# MDM00001.net
KiCad netlist of a schematic drawn in EAGLE
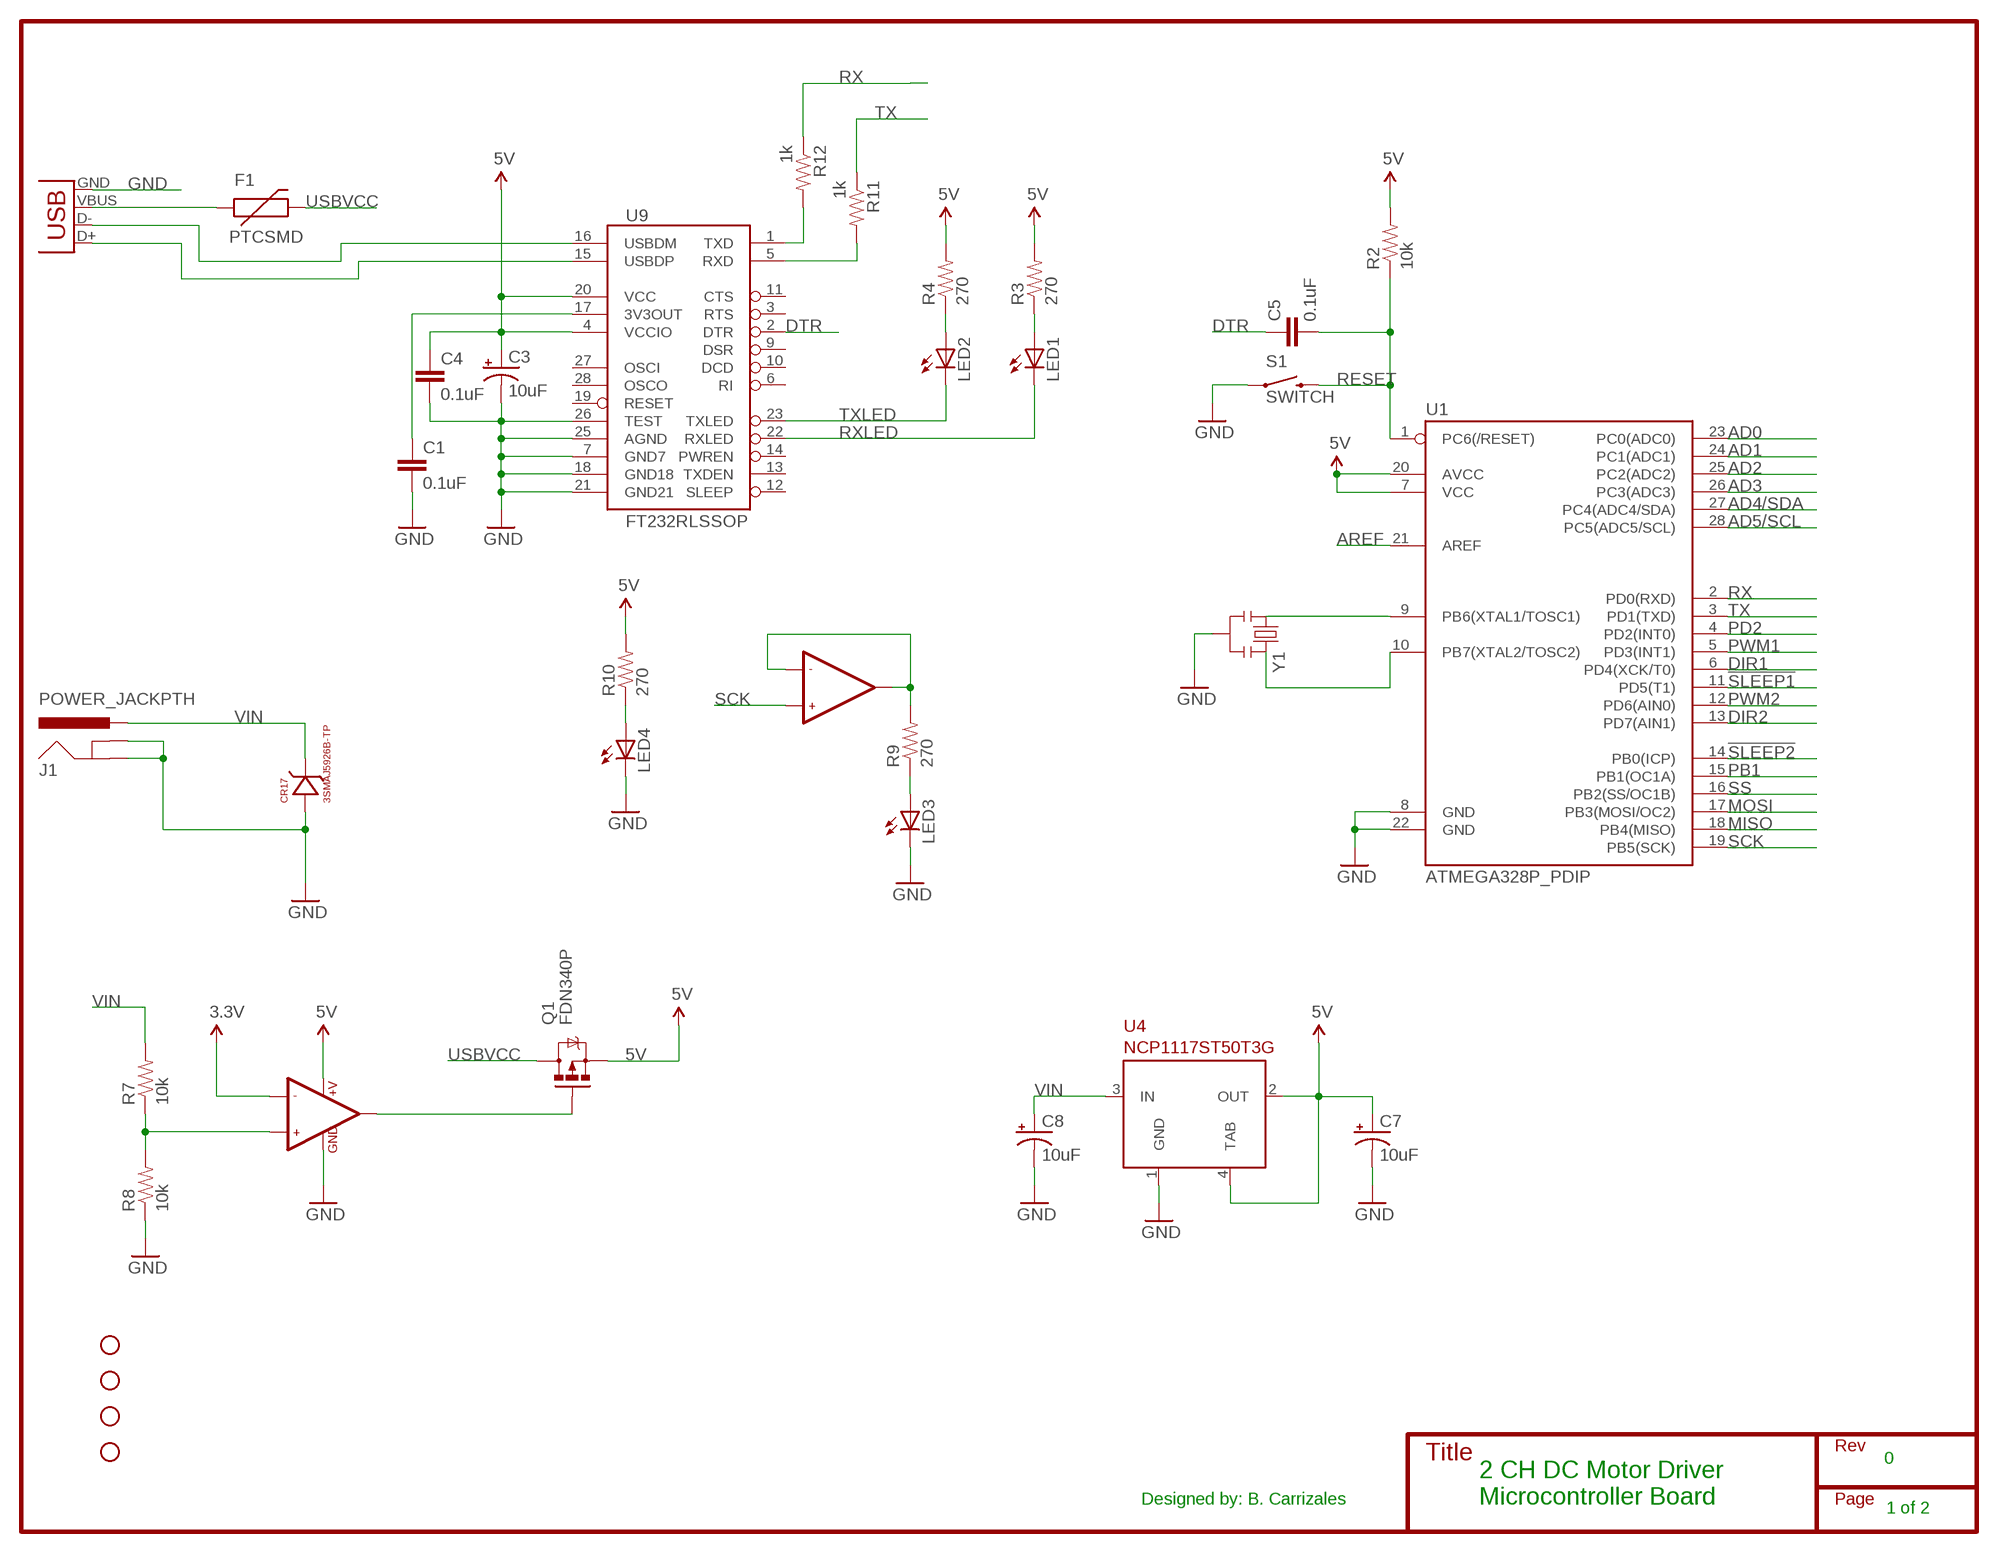
[diagram p0: schematic, sheet 1]
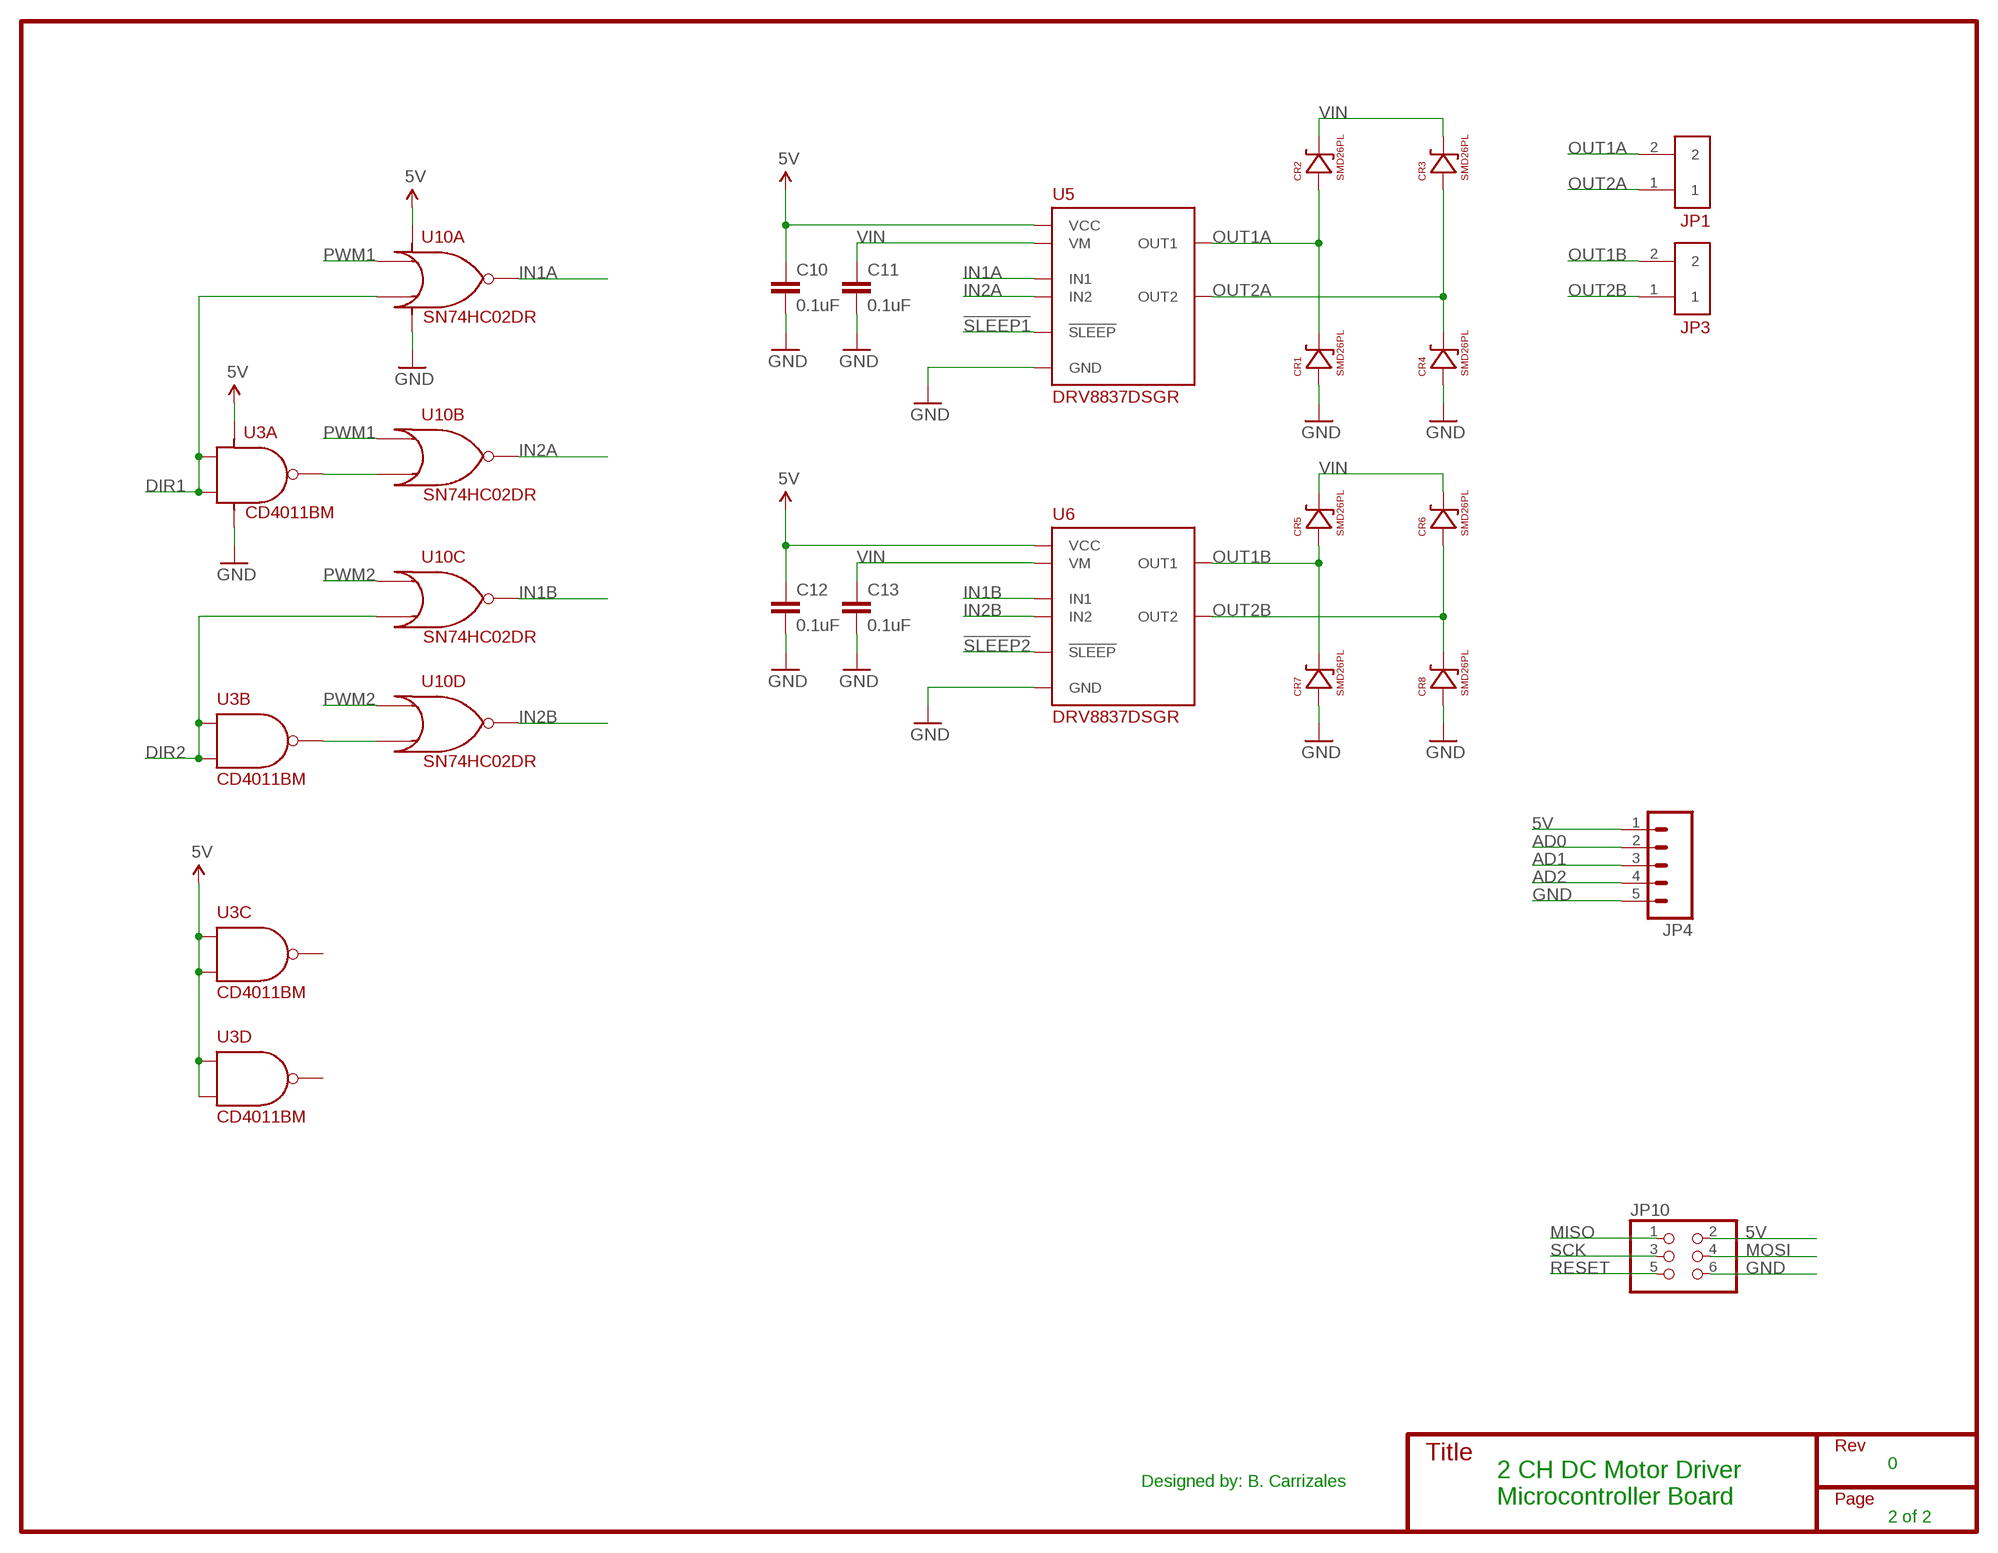
[diagram p1: schematic, sheet 2]

(export (version "E")
  (design (tool "Eeschema 10.0.6"))
  (components
    (comp (ref "C1")
      (value "0.1uF")
      (footprint "eagle-import:0603-CAP")
      (libsource (lib "eagle-import") (part "CAP0603-CAP"))
    )
    (comp (ref "C3")
      (value "10uF")
      (footprint "eagle-import:PANASONIC_BMIN")
      (libsource (lib "eagle-import") (part "CAP_POL_AL"))
    )
    (comp (ref "C4")
      (value "0.1uF")
      (footprint "eagle-import:0603-CAP")
      (libsource (lib "eagle-import") (part "CAP0603-CAP"))
    )
    (comp (ref "C5")
      (value "0.1uF")
      (footprint "eagle-import:0603-CAP")
      (libsource (lib "eagle-import") (part "CAP0603-CAP"))
    )
    (comp (ref "C7")
      (value "10uF")
      (footprint "eagle-import:PANASONIC_BMIN")
      (libsource (lib "eagle-import") (part "CAP_POL_AL"))
    )
    (comp (ref "C8")
      (value "10uF")
      (footprint "eagle-import:PANASONIC_BMIN")
      (libsource (lib "eagle-import") (part "CAP_POL_AL"))
    )
    (comp (ref "CR17")
      (value "3SMAJ5926B-TP")
      (footprint "eagle-import:DO-214AC")
      (fields (field (name "DIGIKEYPART#") "3SMAJ5926B-TPMSCT-ND"))
      (libsource (lib "eagle-import") (part "3SMAJ5926B-TP"))
    )
    (comp (ref "F1")
      (value "PTCSMD")
      (footprint "eagle-import:PTC-1206")
      (libsource (lib "eagle-import") (part "PTCSMD"))
    )
    (comp (ref "J1")
      (value "POWER_JACKPTH")
      (footprint "eagle-import:POWER_JACK_PTH")
      (libsource (lib "eagle-import") (part "POWER_JACKPTH"))
    )
    (comp (ref "JP2")
      (value "USBSMD")
      (footprint "eagle-import:USB-MINIB")
      (libsource (lib "eagle-import") (part "USBSMD"))
    )
    (comp (ref "LED1")
      (value "LED0603")
      (footprint "eagle-import:LED-0603")
      (libsource (lib "eagle-import") (part "LED0603"))
    )
    (comp (ref "LED2")
      (value "LED0603")
      (footprint "eagle-import:LED-0603")
      (libsource (lib "eagle-import") (part "LED0603"))
    )
    (comp (ref "LED3")
      (value "LED0603")
      (footprint "eagle-import:LED-0603")
      (libsource (lib "eagle-import") (part "LED0603"))
    )
    (comp (ref "LED4")
      (value "LED0603")
      (footprint "eagle-import:LED-0603")
      (libsource (lib "eagle-import") (part "LED0603"))
    )
    (comp (ref "Q1")
      (value "FDN340P")
      (footprint "eagle-import:SOT23-3")
      (libsource (lib "eagle-import") (part "MOSFET-PCHANNELSMD"))
    )
    (comp (ref "R2")
      (value "10k")
      (footprint "eagle-import:0603-RES")
      (libsource (lib "eagle-import") (part "RESISTOR0603-RES"))
    )
    (comp (ref "R3")
      (value "270")
      (footprint "eagle-import:0603-RES")
      (libsource (lib "eagle-import") (part "RESISTOR0603-RES"))
    )
    (comp (ref "R4")
      (value "270")
      (footprint "eagle-import:0603-RES")
      (libsource (lib "eagle-import") (part "RESISTOR0603-RES"))
    )
    (comp (ref "R7")
      (value "10k")
      (footprint "eagle-import:0603-RES")
      (libsource (lib "eagle-import") (part "RESISTOR0603-RES"))
    )
    (comp (ref "R8")
      (value "10k")
      (footprint "eagle-import:0603-RES")
      (libsource (lib "eagle-import") (part "RESISTOR0603-RES"))
    )
    (comp (ref "R9")
      (value "270")
      (footprint "eagle-import:0603-RES")
      (libsource (lib "eagle-import") (part "RESISTOR0603-RES"))
    )
    (comp (ref "R10")
      (value "270")
      (footprint "eagle-import:0603-RES")
      (libsource (lib "eagle-import") (part "RESISTOR0603-RES"))
    )
    (comp (ref "R11")
      (value "1k")
      (footprint "eagle-import:0603-RES")
      (libsource (lib "eagle-import") (part "RESISTOR0603-RES"))
    )
    (comp (ref "R12")
      (value "1k")
      (footprint "eagle-import:0603-RES")
      (libsource (lib "eagle-import") (part "RESISTOR0603-RES"))
    )
    (comp (ref "S1")
      (value "SWITCH")
      (footprint "eagle-import:TACTILE-PTH")
      (libsource (lib "eagle-import") (part "SWITCH-MOMENTARY-2PTH"))
    )
    (comp (ref "STANDOFF1")
      (value "STAND-OFF")
      (footprint "eagle-import:STAND-OFF")
      (libsource (lib "eagle-import") (part "STAND-OFF"))
    )
    (comp (ref "STANDOFF2")
      (value "STAND-OFF")
      (footprint "eagle-import:STAND-OFF")
      (libsource (lib "eagle-import") (part "STAND-OFF"))
    )
    (comp (ref "STANDOFF3")
      (value "STAND-OFF")
      (footprint "eagle-import:STAND-OFF")
      (libsource (lib "eagle-import") (part "STAND-OFF"))
    )
    (comp (ref "STANDOFF4")
      (value "STAND-OFF")
      (footprint "eagle-import:STAND-OFF")
      (libsource (lib "eagle-import") (part "STAND-OFF"))
    )
    (comp (ref "U$3")
      (value "LMV358")
      (footprint "eagle-import:SO08")
      (libsource (lib "eagle-import") (part "LMV358"))
    )
    (comp (ref "U1")
      (value "ATMEGA328P_PDIP")
      (footprint "eagle-import:DIL28-3")
      (libsource (lib "eagle-import") (part "ATMEGA328P_PDIP"))
    )
    (comp (ref "U4")
      (value "NCP1117ST50T3G")
      (footprint "eagle-import:SOT223")
      (fields (field (name "DIGIKEYPART#") "NCP1117ST50T3GOSCT-ND"))
      (libsource (lib "eagle-import") (part "NCP1117ST50T3G"))
    )
    (comp (ref "U9")
      (value "FT232RLSSOP")
      (footprint "eagle-import:SSOP28DB")
      (libsource (lib "eagle-import") (part "FT232RLSSOP"))
    )
    (comp (ref "Y1")
      (value "RESONATORPTH")
      (footprint "eagle-import:RESONATOR-PTH")
      (libsource (lib "eagle-import") (part "RESONATORPTH"))
    )
    (comp (ref "C10")
      (value "0.1uF")
      (footprint "eagle-import:0603-CAP")
      (libsource (lib "eagle-import") (part "CAP0603-CAP"))
    )
    (comp (ref "C11")
      (value "0.1uF")
      (footprint "eagle-import:0603-CAP")
      (libsource (lib "eagle-import") (part "CAP0603-CAP"))
    )
    (comp (ref "C12")
      (value "0.1uF")
      (footprint "eagle-import:0603-CAP")
      (libsource (lib "eagle-import") (part "CAP0603-CAP"))
    )
    (comp (ref "C13")
      (value "0.1uF")
      (footprint "eagle-import:0603-CAP")
      (libsource (lib "eagle-import") (part "CAP0603-CAP"))
    )
    (comp (ref "CR1")
      (value "SMD26PL")
      (footprint "eagle-import:SOD-123FL")
      (fields (field (name "DIGIKEYPART#") "SMD26PL-TPMSCT-ND"))
      (libsource (lib "eagle-import") (part "SMD26PL"))
    )
    (comp (ref "CR2")
      (value "SMD26PL")
      (footprint "eagle-import:SOD-123FL")
      (fields (field (name "DIGIKEYPART#") "SMD26PL-TPMSCT-ND"))
      (libsource (lib "eagle-import") (part "SMD26PL"))
    )
    (comp (ref "CR3")
      (value "SMD26PL")
      (footprint "eagle-import:SOD-123FL")
      (fields (field (name "DIGIKEYPART#") "SMD26PL-TPMSCT-ND"))
      (libsource (lib "eagle-import") (part "SMD26PL"))
    )
    (comp (ref "CR4")
      (value "SMD26PL")
      (footprint "eagle-import:SOD-123FL")
      (fields (field (name "DIGIKEYPART#") "SMD26PL-TPMSCT-ND"))
      (libsource (lib "eagle-import") (part "SMD26PL"))
    )
    (comp (ref "CR5")
      (value "SMD26PL")
      (footprint "eagle-import:SOD-123FL")
      (fields (field (name "DIGIKEYPART#") "SMD26PL-TPMSCT-ND"))
      (libsource (lib "eagle-import") (part "SMD26PL"))
    )
    (comp (ref "CR6")
      (value "SMD26PL")
      (footprint "eagle-import:SOD-123FL")
      (fields (field (name "DIGIKEYPART#") "SMD26PL-TPMSCT-ND"))
      (libsource (lib "eagle-import") (part "SMD26PL"))
    )
    (comp (ref "CR7")
      (value "SMD26PL")
      (footprint "eagle-import:SOD-123FL")
      (fields (field (name "DIGIKEYPART#") "SMD26PL-TPMSCT-ND"))
      (libsource (lib "eagle-import") (part "SMD26PL"))
    )
    (comp (ref "CR8")
      (value "SMD26PL")
      (footprint "eagle-import:SOD-123FL")
      (fields (field (name "DIGIKEYPART#") "SMD26PL-TPMSCT-ND"))
      (libsource (lib "eagle-import") (part "SMD26PL"))
    )
    (comp (ref "JP1")
      (value "2-TERMINAL")
      (footprint "eagle-import:OSTTA020161")
      (fields (field (name "DIGIKEYPART#") "ED2561-ND") (field (name "PART#") "OSTTA020161"))
      (libsource (lib "eagle-import") (part "2-TERMINAL"))
    )
    (comp (ref "JP3")
      (value "2-TERMINAL")
      (footprint "eagle-import:OSTTA020161")
      (fields (field (name "DIGIKEYPART#") "ED2561-ND") (field (name "PART#") "OSTTA020161"))
      (libsource (lib "eagle-import") (part "2-TERMINAL"))
    )
    (comp (ref "JP4")
      (value "M05PTH")
      (footprint "eagle-import:1X05")
      (libsource (lib "eagle-import") (part "M05PTH"))
    )
    (comp (ref "JP10")
      (value "PINHD-2X3")
      (footprint "eagle-import:2X03")
      (libsource (lib "eagle-import") (part "PINHD-2X3"))
    )
    (comp (ref "U3")
      (value "CD4011BM")
      (footprint "eagle-import:14-SOIC")
      (fields (field (name "DIGIKEYPART#") "296-14474-1-ND"))
      (libsource (lib "eagle-import") (part "CD4011BM"))
    )
    (comp (ref "U5")
      (value "DRV8837DSGR")
      (footprint "eagle-import:8-WSON")
      (fields (field (name "DIGIKEYPART#") "296-34806-1-ND"))
      (libsource (lib "eagle-import") (part "DRV8837DSGR"))
    )
    (comp (ref "U6")
      (value "DRV8837DSGR")
      (footprint "eagle-import:8-WSON")
      (fields (field (name "DIGIKEYPART#") "296-34806-1-ND"))
      (libsource (lib "eagle-import") (part "DRV8837DSGR"))
    )
    (comp (ref "U10")
      (value "SN74HC02DR")
      (footprint "eagle-import:14-SOIC")
      (fields (field (name "DIGIKEYPART#") "296-1188-1-ND"))
      (libsource (lib "eagle-import") (part "SN74HC02DR"))
    )
  )
  (nets
    (net (code "1") (name "3.3V") (class "Default")
      (node (ref "U$3") (pin "2") (pinfunction "-IN1_2") (pintype "input"))
    )
    (net (code "2") (name "5V") (class "Default")
      (node (ref "C10") (pin "1") (pinfunction "1_1") (pintype "passive"))
      (node (ref "C12") (pin "1") (pinfunction "1_1") (pintype "passive"))
      (node (ref "C3") (pin "+") (pinfunction "+_+") (pintype "passive"))
      (node (ref "C4") (pin "1") (pinfunction "1_1") (pintype "passive"))
      (node (ref "C7") (pin "+") (pinfunction "+_+") (pintype "passive"))
      (node (ref "JP10") (pin "2") (pinfunction "2_2") (pintype "passive"))
      (node (ref "JP4") (pin "1") (pinfunction "1_1") (pintype "passive"))
      (node (ref "Q1") (pin "2") (pinfunction "S_2") (pintype "passive"))
      (node (ref "R10") (pin "2") (pinfunction "2_2") (pintype "passive"))
      (node (ref "R2") (pin "2") (pinfunction "2_2") (pintype "passive"))
      (node (ref "R3") (pin "2") (pinfunction "2_2") (pintype "passive"))
      (node (ref "R4") (pin "2") (pinfunction "2_2") (pintype "passive"))
      (node (ref "U$3") (pin "8") (pinfunction "+V_8") (pintype "power_in"))
      (node (ref "U1") (pin "20") (pinfunction "AVCC_20") (pintype "bidirectional"))
      (node (ref "U1") (pin "7") (pinfunction "VCC_7") (pintype "bidirectional"))
      (node (ref "U10") (pin "14") (pinfunction "14_14") (pintype "power_in"))
      (node (ref "U3") (pin "12") (pinfunction "I0_12") (pintype "input"))
      (node (ref "U3") (pin "13") (pinfunction "I1_13") (pintype "input"))
      (node (ref "U3") (pin "14") (pinfunction "14_14") (pintype "power_in"))
      (node (ref "U3") (pin "8") (pinfunction "I0_8") (pintype "input"))
      (node (ref "U3") (pin "9") (pinfunction "I1_9") (pintype "input"))
      (node (ref "U4") (pin "2") (pinfunction "OUT_2") (pintype "bidirectional"))
      (node (ref "U4") (pin "4") (pinfunction "TAB_4") (pintype "bidirectional"))
      (node (ref "U5") (pin "P$8") (pinfunction "VCC_P$8") (pintype "bidirectional"))
      (node (ref "U6") (pin "P$8") (pinfunction "VCC_P$8") (pintype "bidirectional"))
      (node (ref "U9") (pin "20") (pinfunction "VCC_20") (pintype "power_in"))
      (node (ref "U9") (pin "4") (pinfunction "VCCIO_4") (pintype "power_in"))
    )
    (net (code "3") (name "AD0") (class "Default")
      (node (ref "JP4") (pin "2") (pinfunction "2_2") (pintype "passive"))
      (node (ref "U1") (pin "23") (pinfunction "PC0(ADC0)_23") (pintype "bidirectional"))
    )
    (net (code "4") (name "AD1") (class "Default")
      (node (ref "JP4") (pin "3") (pinfunction "3_3") (pintype "passive"))
      (node (ref "U1") (pin "24") (pinfunction "PC1(ADC1)_24") (pintype "bidirectional"))
    )
    (net (code "5") (name "AD2") (class "Default")
      (node (ref "JP4") (pin "4") (pinfunction "4_4") (pintype "passive"))
      (node (ref "U1") (pin "25") (pinfunction "PC2(ADC2)_25") (pintype "bidirectional"))
    )
    (net (code "6") (name "AD3") (class "Default")
      (node (ref "U1") (pin "26") (pinfunction "PC3(ADC3)_26") (pintype "bidirectional"))
    )
    (net (code "7") (name "AD4{slash}SDA") (class "Default")
      (node (ref "U1") (pin "27") (pinfunction "PC4(ADC4/SDA)_27") (pintype "bidirectional"))
    )
    (net (code "8") (name "AD5{slash}SCL") (class "Default")
      (node (ref "U1") (pin "28") (pinfunction "PC5(ADC5/SCL)_28") (pintype "bidirectional"))
    )
    (net (code "9") (name "AREF") (class "Default")
      (node (ref "U1") (pin "21") (pinfunction "AREF_21") (pintype "bidirectional"))
    )
    (net (code "10") (name "DIR1") (class "Default")
      (node (ref "U1") (pin "6") (pinfunction "PD4(XCK/T0)_6") (pintype "bidirectional"))
      (node (ref "U10") (pin "3") (pinfunction "I1_3") (pintype "input"))
      (node (ref "U3") (pin "1") (pinfunction "I0_1") (pintype "input"))
      (node (ref "U3") (pin "2") (pinfunction "I1_2") (pintype "input"))
    )
    (net (code "11") (name "DIR2") (class "Default")
      (node (ref "U1") (pin "13") (pinfunction "PD7(AIN1)_13") (pintype "bidirectional"))
      (node (ref "U10") (pin "9") (pinfunction "I1_9") (pintype "input"))
      (node (ref "U3") (pin "5") (pinfunction "I0_5") (pintype "input"))
      (node (ref "U3") (pin "6") (pinfunction "I1_6") (pintype "input"))
    )
    (net (code "12") (name "DTR") (class "Default")
      (node (ref "C5") (pin "1") (pinfunction "1_1") (pintype "passive"))
      (node (ref "U9") (pin "2") (pinfunction "DTR_2") (pintype "output"))
    )
    (net (code "13") (name "GND") (class "Default")
      (node (ref "C1") (pin "2") (pinfunction "2_2") (pintype "passive"))
      (node (ref "C10") (pin "2") (pinfunction "2_2") (pintype "passive"))
      (node (ref "C11") (pin "2") (pinfunction "2_2") (pintype "passive"))
      (node (ref "C12") (pin "2") (pinfunction "2_2") (pintype "passive"))
      (node (ref "C13") (pin "2") (pinfunction "2_2") (pintype "passive"))
      (node (ref "C3") (pin "-") (pinfunction "-_-") (pintype "passive"))
      (node (ref "C4") (pin "2") (pinfunction "2_2") (pintype "passive"))
      (node (ref "C7") (pin "-") (pinfunction "-_-") (pintype "passive"))
      (node (ref "C8") (pin "-") (pinfunction "-_-") (pintype "passive"))
      (node (ref "CR1") (pin "1") (pinfunction "1_1") (pintype "bidirectional"))
      (node (ref "CR17") (pin "AN") (pinfunction "AN_AN") (pintype "bidirectional"))
      (node (ref "CR4") (pin "1") (pinfunction "1_1") (pintype "bidirectional"))
      (node (ref "CR7") (pin "1") (pinfunction "1_1") (pintype "bidirectional"))
      (node (ref "CR8") (pin "1") (pinfunction "1_1") (pintype "bidirectional"))
      (node (ref "J1") (pin "GND") (pinfunction "GND_GND") (pintype "bidirectional"))
      (node (ref "J1") (pin "GNDBREAK") (pinfunction "GNDBREAK_GNDBREAK") (pintype "bidirectional"))
      (node (ref "JP10") (pin "6") (pinfunction "6_6") (pintype "passive"))
      (node (ref "JP2") (pin "GND") (pinfunction "GND_GND") (pintype "bidirectional"))
      (node (ref "JP4") (pin "5") (pinfunction "5_5") (pintype "passive"))
      (node (ref "LED3") (pin "C") (pinfunction "C_C") (pintype "passive"))
      (node (ref "LED4") (pin "C") (pinfunction "C_C") (pintype "passive"))
      (node (ref "R8") (pin "1") (pinfunction "1_1") (pintype "passive"))
      (node (ref "S1") (pin "1") (pinfunction "1_1") (pintype "passive"))
      (node (ref "U$3") (pin "4") (pinfunction "GND_4") (pintype "power_in"))
      (node (ref "U1") (pin "22") (pinfunction "GND_22") (pintype "bidirectional"))
      (node (ref "U1") (pin "8") (pinfunction "GND_8") (pintype "bidirectional"))
      (node (ref "U10") (pin "7") (pinfunction "7_7") (pintype "power_in"))
      (node (ref "U3") (pin "7") (pinfunction "7_7") (pintype "power_in"))
      (node (ref "U4") (pin "1") (pinfunction "GND_1") (pintype "bidirectional"))
      (node (ref "U5") (pin "P$4") (pinfunction "GND_P$4") (pintype "bidirectional"))
      (node (ref "U6") (pin "P$4") (pinfunction "GND_P$4") (pintype "bidirectional"))
      (node (ref "U9") (pin "18") (pinfunction "GND18_18") (pintype "power_in"))
      (node (ref "U9") (pin "21") (pinfunction "GND21_21") (pintype "power_in"))
      (node (ref "U9") (pin "25") (pinfunction "AGND_25") (pintype "power_in"))
      (node (ref "U9") (pin "26") (pinfunction "TEST_26") (pintype "input"))
      (node (ref "U9") (pin "7") (pinfunction "GND7_7") (pintype "power_in"))
      (node (ref "Y1") (pin "2") (pinfunction "2_2") (pintype "passive"))
    )
    (net (code "14") (name "IN1A") (class "Default")
      (node (ref "U10") (pin "1") (pinfunction "O1_1") (pintype "output"))
      (node (ref "U5") (pin "P$6") (pinfunction "IN1_P$6") (pintype "bidirectional"))
    )
    (net (code "15") (name "IN1B") (class "Default")
      (node (ref "U10") (pin "10") (pinfunction "O1_10") (pintype "output"))
      (node (ref "U6") (pin "P$6") (pinfunction "IN1_P$6") (pintype "bidirectional"))
    )
    (net (code "16") (name "IN2A") (class "Default")
      (node (ref "U10") (pin "4") (pinfunction "O1_4") (pintype "output"))
      (node (ref "U5") (pin "P$5") (pinfunction "IN2_P$5") (pintype "bidirectional"))
    )
    (net (code "17") (name "IN2B") (class "Default")
      (node (ref "U10") (pin "13") (pinfunction "O1_13") (pintype "output"))
      (node (ref "U6") (pin "P$5") (pinfunction "IN2_P$5") (pintype "bidirectional"))
    )
    (net (code "18") (name "MISO") (class "Default")
      (node (ref "JP10") (pin "1") (pinfunction "1_1") (pintype "passive"))
      (node (ref "U1") (pin "18") (pinfunction "PB4(MISO)_18") (pintype "bidirectional"))
    )
    (net (code "19") (name "MOSI") (class "Default")
      (node (ref "JP10") (pin "4") (pinfunction "4_4") (pintype "passive"))
      (node (ref "U1") (pin "17") (pinfunction "PB3(MOSI/OC2)_17") (pintype "bidirectional"))
    )
    (net (code "20") (name "Net-(F1-Pad1)") (class "Default")
      (node (ref "F1") (pin "1") (pinfunction "1_1") (pintype "bidirectional"))
      (node (ref "JP2") (pin "VBUS") (pinfunction "VBUS_VBUS") (pintype "bidirectional"))
    )
    (net (code "21") (name "Net-(LED1-PadA)") (class "Default")
      (node (ref "LED1") (pin "A") (pinfunction "A_A") (pintype "passive"))
      (node (ref "R3") (pin "1") (pinfunction "1_1") (pintype "passive"))
    )
    (net (code "22") (name "Net-(LED2-PadA)") (class "Default")
      (node (ref "LED2") (pin "A") (pinfunction "A_A") (pintype "passive"))
      (node (ref "R4") (pin "1") (pinfunction "1_1") (pintype "passive"))
    )
    (net (code "23") (name "Net-(LED3-PadA)") (class "Default")
      (node (ref "LED3") (pin "A") (pinfunction "A_A") (pintype "passive"))
      (node (ref "R9") (pin "1") (pinfunction "1_1") (pintype "passive"))
    )
    (net (code "24") (name "Net-(LED4-PadA)") (class "Default")
      (node (ref "LED4") (pin "A") (pinfunction "A_A") (pintype "passive"))
      (node (ref "R10") (pin "1") (pinfunction "1_1") (pintype "passive"))
    )
    (net (code "25") (name "Net-(Q1-G)") (class "Default")
      (node (ref "Q1") (pin "1") (pinfunction "G_1") (pintype "passive"))
      (node (ref "U$3") (pin "1") (pinfunction "OUT1_1") (pintype "output"))
    )
    (net (code "26") (name "Net-(U$3A-+IN1)") (class "Default")
      (node (ref "R7") (pin "1") (pinfunction "1_1") (pintype "passive"))
      (node (ref "R8") (pin "2") (pinfunction "2_2") (pintype "passive"))
      (node (ref "U$3") (pin "3") (pinfunction "+IN1_3") (pintype "input"))
    )
    (net (code "27") (name "Net-(U$3B--IN2)") (class "Default")
      (node (ref "R9") (pin "2") (pinfunction "2_2") (pintype "passive"))
      (node (ref "U$3") (pin "6") (pinfunction "-IN2_6") (pintype "input"))
      (node (ref "U$3") (pin "7") (pinfunction "OUT2_7") (pintype "output"))
    )
    (net (code "28") (name "Net-(U1-PB6(XTAL1{slash}TOSC1))") (class "Default")
      (node (ref "U1") (pin "9") (pinfunction "PB6(XTAL1/TOSC1)_9") (pintype "bidirectional"))
      (node (ref "Y1") (pin "1") (pinfunction "1_1") (pintype "passive"))
    )
    (net (code "29") (name "Net-(U1-PB7(XTAL2{slash}TOSC2))") (class "Default")
      (node (ref "U1") (pin "10") (pinfunction "PB7(XTAL2/TOSC2)_10") (pintype "bidirectional"))
      (node (ref "Y1") (pin "3") (pinfunction "3_3") (pintype "passive"))
    )
    (net (code "30") (name "Net-(U9-3V3OUT)") (class "Default")
      (node (ref "C1") (pin "1") (pinfunction "1_1") (pintype "passive"))
      (node (ref "U9") (pin "17") (pinfunction "3V3OUT_17") (pintype "output"))
    )
    (net (code "31") (name "Net-(U9-RXD)") (class "Default")
      (node (ref "R11") (pin "2") (pinfunction "2_2") (pintype "passive"))
      (node (ref "U9") (pin "5") (pinfunction "RXD_5") (pintype "input"))
    )
    (net (code "32") (name "Net-(U9-TXD)") (class "Default")
      (node (ref "R12") (pin "2") (pinfunction "2_2") (pintype "passive"))
      (node (ref "U9") (pin "1") (pinfunction "TXD_1") (pintype "output"))
    )
    (net (code "33") (name "Net-(U9-USBDM)") (class "Default")
      (node (ref "JP2") (pin "D-") (pinfunction "D-_D-") (pintype "bidirectional"))
      (node (ref "U9") (pin "16") (pinfunction "USBDM_16") (pintype "bidirectional"))
    )
    (net (code "34") (name "Net-(U9-USBDP)") (class "Default")
      (node (ref "JP2") (pin "D+") (pinfunction "D+_D+") (pintype "bidirectional"))
      (node (ref "U9") (pin "15") (pinfunction "USBDP_15") (pintype "bidirectional"))
    )
    (net (code "35") (name "Net-(U10B-I1)") (class "Default")
      (node (ref "U10") (pin "6") (pinfunction "I1_6") (pintype "input"))
      (node (ref "U3") (pin "3") (pinfunction "O1_3") (pintype "output"))
    )
    (net (code "36") (name "Net-(U10D-I1)") (class "Default")
      (node (ref "U10") (pin "12") (pinfunction "I1_12") (pintype "input"))
      (node (ref "U3") (pin "4") (pinfunction "O1_4") (pintype "output"))
    )
    (net (code "37") (name "OUT1A") (class "Default")
      (node (ref "CR1") (pin "2") (pinfunction "2_2") (pintype "bidirectional"))
      (node (ref "CR2") (pin "1") (pinfunction "1_1") (pintype "bidirectional"))
      (node (ref "JP1") (pin "2") (pinfunction "2_2") (pintype "bidirectional"))
      (node (ref "U5") (pin "P$2") (pinfunction "OUT1_P$2") (pintype "bidirectional"))
    )
    (net (code "38") (name "OUT1B") (class "Default")
      (node (ref "CR5") (pin "1") (pinfunction "1_1") (pintype "bidirectional"))
      (node (ref "CR7") (pin "2") (pinfunction "2_2") (pintype "bidirectional"))
      (node (ref "JP3") (pin "2") (pinfunction "2_2") (pintype "bidirectional"))
      (node (ref "U6") (pin "P$2") (pinfunction "OUT1_P$2") (pintype "bidirectional"))
    )
    (net (code "39") (name "OUT2A") (class "Default")
      (node (ref "CR3") (pin "1") (pinfunction "1_1") (pintype "bidirectional"))
      (node (ref "CR4") (pin "2") (pinfunction "2_2") (pintype "bidirectional"))
      (node (ref "JP1") (pin "1") (pinfunction "1_1") (pintype "bidirectional"))
      (node (ref "U5") (pin "P$3") (pinfunction "OUT2_P$3") (pintype "bidirectional"))
    )
    (net (code "40") (name "OUT2B") (class "Default")
      (node (ref "CR6") (pin "1") (pinfunction "1_1") (pintype "bidirectional"))
      (node (ref "CR8") (pin "2") (pinfunction "2_2") (pintype "bidirectional"))
      (node (ref "JP3") (pin "1") (pinfunction "1_1") (pintype "bidirectional"))
      (node (ref "U6") (pin "P$3") (pinfunction "OUT2_P$3") (pintype "bidirectional"))
    )
    (net (code "41") (name "PB1") (class "Default")
      (node (ref "U1") (pin "15") (pinfunction "PB1(OC1A)_15") (pintype "bidirectional"))
    )
    (net (code "42") (name "PD2") (class "Default")
      (node (ref "U1") (pin "4") (pinfunction "PD2(INT0)_4") (pintype "bidirectional"))
    )
    (net (code "43") (name "PWM1") (class "Default")
      (node (ref "U1") (pin "5") (pinfunction "PD3(INT1)_5") (pintype "bidirectional"))
      (node (ref "U10") (pin "2") (pinfunction "I0_2") (pintype "input"))
      (node (ref "U10") (pin "5") (pinfunction "I0_5") (pintype "input"))
    )
    (net (code "44") (name "PWM2") (class "Default")
      (node (ref "U1") (pin "12") (pinfunction "PD6(AIN0)_12") (pintype "bidirectional"))
      (node (ref "U10") (pin "11") (pinfunction "I0_11") (pintype "input"))
      (node (ref "U10") (pin "8") (pinfunction "I0_8") (pintype "input"))
    )
    (net (code "45") (name "RESET") (class "Default")
      (node (ref "C5") (pin "2") (pinfunction "2_2") (pintype "passive"))
      (node (ref "JP10") (pin "5") (pinfunction "5_5") (pintype "passive"))
      (node (ref "R2") (pin "1") (pinfunction "1_1") (pintype "passive"))
      (node (ref "S1") (pin "3") (pinfunction "2_3") (pintype "passive"))
      (node (ref "U1") (pin "1") (pinfunction "PC6(/RESET)_1") (pintype "bidirectional"))
    )
    (net (code "46") (name "RX") (class "Default")
      (node (ref "R12") (pin "1") (pinfunction "1_1") (pintype "passive"))
      (node (ref "U1") (pin "2") (pinfunction "PD0(RXD)_2") (pintype "bidirectional"))
    )
    (net (code "47") (name "RXLED") (class "Default")
      (node (ref "LED1") (pin "C") (pinfunction "C_C") (pintype "passive"))
      (node (ref "U9") (pin "22") (pinfunction "RXLED_22") (pintype "input"))
    )
    (net (code "48") (name "SCK") (class "Default")
      (node (ref "JP10") (pin "3") (pinfunction "3_3") (pintype "passive"))
      (node (ref "U$3") (pin "5") (pinfunction "+IN2_5") (pintype "input"))
      (node (ref "U1") (pin "19") (pinfunction "PB5(SCK)_19") (pintype "bidirectional"))
    )
    (net (code "49") (name "SS") (class "Default")
      (node (ref "U1") (pin "16") (pinfunction "PB2(SS/OC1B)_16") (pintype "bidirectional"))
    )
    (net (code "50") (name "TX") (class "Default")
      (node (ref "R11") (pin "1") (pinfunction "1_1") (pintype "passive"))
      (node (ref "U1") (pin "3") (pinfunction "PD1(TXD)_3") (pintype "bidirectional"))
    )
    (net (code "51") (name "TXLED") (class "Default")
      (node (ref "LED2") (pin "C") (pinfunction "C_C") (pintype "passive"))
      (node (ref "U9") (pin "23") (pinfunction "TXLED_23") (pintype "input"))
    )
    (net (code "52") (name "USBVCC") (class "Default")
      (node (ref "F1") (pin "2") (pinfunction "2_2") (pintype "bidirectional"))
      (node (ref "Q1") (pin "3") (pinfunction "D_3") (pintype "passive"))
    )
    (net (code "53") (name "VIN") (class "Default")
      (node (ref "C11") (pin "1") (pinfunction "1_1") (pintype "passive"))
      (node (ref "C13") (pin "1") (pinfunction "1_1") (pintype "passive"))
      (node (ref "C8") (pin "+") (pinfunction "+_+") (pintype "passive"))
      (node (ref "CR17") (pin "CAT") (pinfunction "CAT_CAT") (pintype "bidirectional"))
      (node (ref "CR2") (pin "2") (pinfunction "2_2") (pintype "bidirectional"))
      (node (ref "CR3") (pin "2") (pinfunction "2_2") (pintype "bidirectional"))
      (node (ref "CR5") (pin "2") (pinfunction "2_2") (pintype "bidirectional"))
      (node (ref "CR6") (pin "2") (pinfunction "2_2") (pintype "bidirectional"))
      (node (ref "J1") (pin "PWR") (pinfunction "PWR_PWR") (pintype "bidirectional"))
      (node (ref "R7") (pin "2") (pinfunction "2_2") (pintype "passive"))
      (node (ref "U4") (pin "3") (pinfunction "IN_3") (pintype "bidirectional"))
      (node (ref "U5") (pin "P$1") (pinfunction "VM_P$1") (pintype "bidirectional"))
      (node (ref "U6") (pin "P$1") (pinfunction "VM_P$1") (pintype "bidirectional"))
    )
    (net (code "54") (name "unconnected-(U3C-O1-Pad10)") (class "Default")
      (node (ref "U3") (pin "10") (pinfunction "O1_10") (pintype "output"))
    )
    (net (code "55") (name "unconnected-(U3D-O1-Pad11)") (class "Default")
      (node (ref "U3") (pin "11") (pinfunction "O1_11") (pintype "output"))
    )
    (net (code "56") (name "unconnected-(U9-CTS-Pad11)") (class "Default")
      (node (ref "U9") (pin "11") (pinfunction "CTS_11") (pintype "input"))
    )
    (net (code "57") (name "unconnected-(U9-DCD-Pad10)") (class "Default")
      (node (ref "U9") (pin "10") (pinfunction "DCD_10") (pintype "input"))
    )
    (net (code "58") (name "unconnected-(U9-DSR-Pad9)") (class "Default")
      (node (ref "U9") (pin "9") (pinfunction "DSR_9") (pintype "input"))
    )
    (net (code "59") (name "unconnected-(U9-OSCI-Pad27)") (class "Default")
      (node (ref "U9") (pin "27") (pinfunction "OSCI_27") (pintype "input"))
    )
    (net (code "60") (name "unconnected-(U9-OSCO-Pad28)") (class "Default")
      (node (ref "U9") (pin "28") (pinfunction "OSCO_28") (pintype "output"))
    )
    (net (code "61") (name "unconnected-(U9-PWREN-Pad14)") (class "Default")
      (node (ref "U9") (pin "14") (pinfunction "PWREN_14") (pintype "input"))
    )
    (net (code "62") (name "unconnected-(U9-RESET-Pad19)") (class "Default")
      (node (ref "U9") (pin "19") (pinfunction "RESET_19") (pintype "input"))
    )
    (net (code "63") (name "unconnected-(U9-RI-Pad6)") (class "Default")
      (node (ref "U9") (pin "6") (pinfunction "RI_6") (pintype "input"))
    )
    (net (code "64") (name "unconnected-(U9-RTS-Pad3)") (class "Default")
      (node (ref "U9") (pin "3") (pinfunction "RTS_3") (pintype "output"))
    )
    (net (code "65") (name "unconnected-(U9-SLEEP-Pad12)") (class "Default")
      (node (ref "U9") (pin "12") (pinfunction "SLEEP_12") (pintype "input"))
    )
    (net (code "66") (name "unconnected-(U9-TXDEN-Pad13)") (class "Default")
      (node (ref "U9") (pin "13") (pinfunction "TXDEN_13") (pintype "input"))
    )
    (net (code "67") (name "~{SLEEP1}") (class "Default")
      (node (ref "U1") (pin "11") (pinfunction "PD5(T1)_11") (pintype "bidirectional"))
      (node (ref "U5") (pin "P$7") (pinfunction "~{SLEEP}_P$7") (pintype "bidirectional"))
    )
    (net (code "68") (name "~{SLEEP2}") (class "Default")
      (node (ref "U1") (pin "14") (pinfunction "PB0(ICP)_14") (pintype "bidirectional"))
      (node (ref "U6") (pin "P$7") (pinfunction "~{SLEEP}_P$7") (pintype "bidirectional"))
    )
  )
)
